# bldc.net
KiCad netlist of a schematic drawn in EAGLE
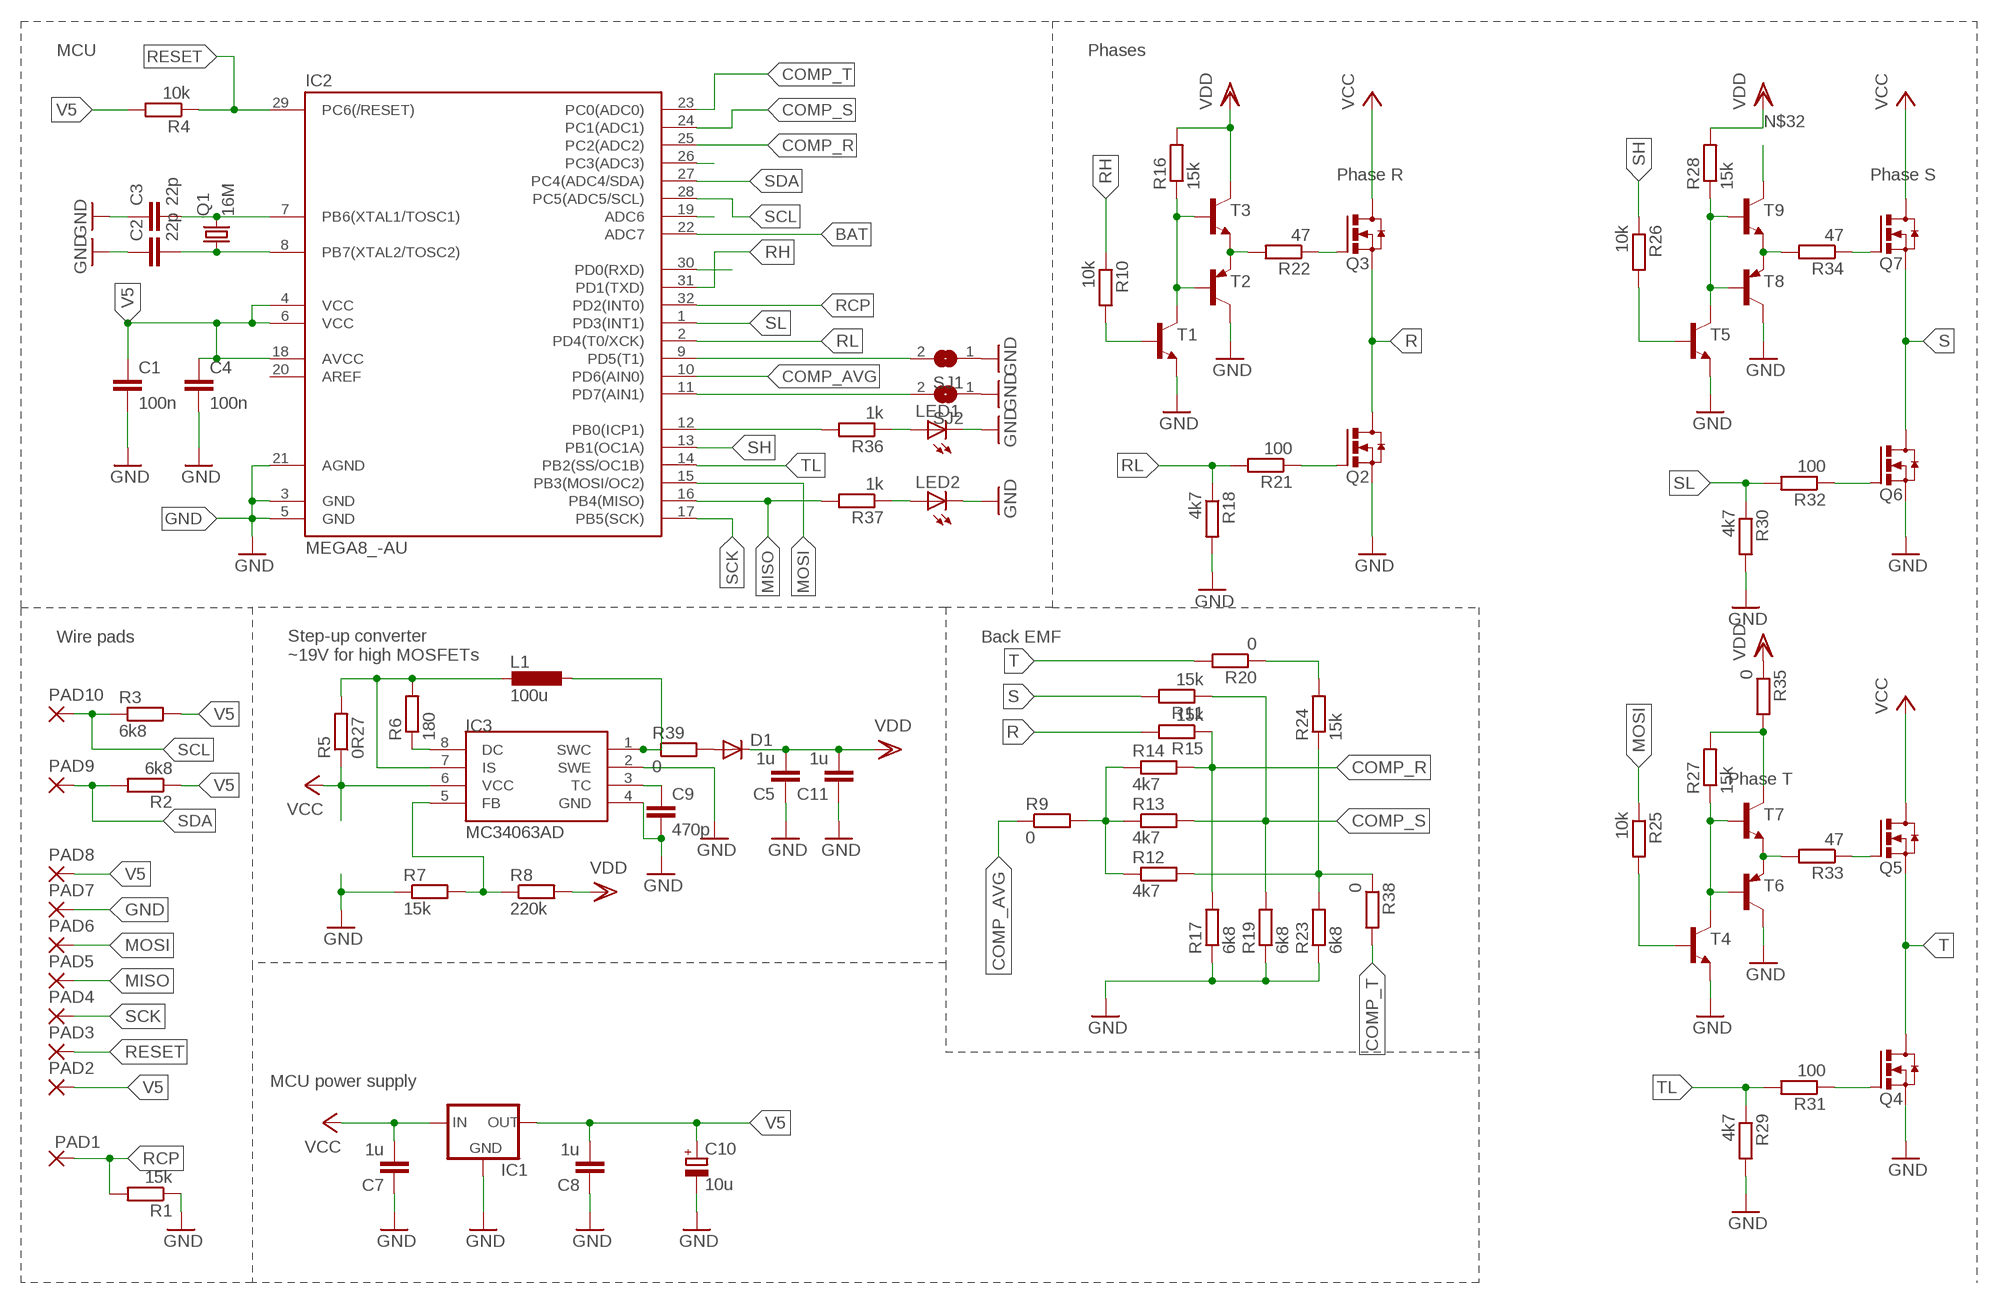
[diagram p0: schematic, sheet 1]

(export (version "E")
  (design (tool "Eeschema 10.0.6"))
  (components
    (comp (ref "C1")
      (value "100n")
      (footprint "eagle-import:C0805K")
      (libsource (lib "eagle-import") (part "rcl2_C-EUC0805K"))
    )
    (comp (ref "C2")
      (value "22p")
      (footprint "eagle-import:C0805K")
      (libsource (lib "eagle-import") (part "rcl2_C-EUC0805K"))
    )
    (comp (ref "C3")
      (value "22p")
      (footprint "eagle-import:C0805K")
      (libsource (lib "eagle-import") (part "rcl2_C-EUC0805K"))
    )
    (comp (ref "C4")
      (value "100n")
      (footprint "eagle-import:C0805K")
      (libsource (lib "eagle-import") (part "rcl2_C-EUC0805K"))
    )
    (comp (ref "C5")
      (value "1u")
      (footprint "eagle-import:C0805K")
      (libsource (lib "eagle-import") (part "rcl2_C-EUC0805K"))
    )
    (comp (ref "C7")
      (value "1u")
      (footprint "eagle-import:C0805K")
      (libsource (lib "eagle-import") (part "rcl2_C-EUC0805K"))
    )
    (comp (ref "C8")
      (value "1u")
      (footprint "eagle-import:C0805K")
      (libsource (lib "eagle-import") (part "rcl2_C-EUC0805K"))
    )
    (comp (ref "C9")
      (value "470p")
      (footprint "eagle-import:C0805K")
      (libsource (lib "eagle-import") (part "C-EUC0805K"))
    )
    (comp (ref "C10")
      (value "10u")
      (footprint "eagle-import:E2,5RE")
      (libsource (lib "eagle-import") (part "CPOL-EUE2.5-4V"))
    )
    (comp (ref "C11")
      (value "1u")
      (footprint "eagle-import:C0805K")
      (libsource (lib "eagle-import") (part "rcl2_C-EUC0805K"))
    )
    (comp (ref "D1")
      (value "DIODE-SOD80C")
      (footprint "eagle-import:SOD80C")
      (libsource (lib "eagle-import") (part "DIODE-SOD80C"))
    )
    (comp (ref "IC1")
      (value "LM1117TO252")
      (footprint "eagle-import:TO252")
      (libsource (lib "eagle-import") (part "LM1117TO252"))
    )
    (comp (ref "IC2")
      (value "MEGA8_-AU")
      (footprint "eagle-import:TQFP32-08")
      (libsource (lib "eagle-import") (part "MEGA8_-AU"))
    )
    (comp (ref "IC3")
      (value "MC34063AD")
      (footprint "eagle-import:SOIC8")
      (libsource (lib "eagle-import") (part "MC34063AD"))
    )
    (comp (ref "L1")
      (value "100u")
      (footprint "eagle-import:0204_7")
      (libsource (lib "eagle-import") (part "L-EU0204/7"))
    )
    (comp (ref "LED1")
      (value "LEDCHIPLED_0805")
      (footprint "eagle-import:CHIPLED_0805")
      (libsource (lib "eagle-import") (part "LEDCHIPLED_0805"))
    )
    (comp (ref "LED2")
      (value "LEDCHIPLED_0805")
      (footprint "eagle-import:CHIPLED_0805")
      (libsource (lib "eagle-import") (part "LEDCHIPLED_0805"))
    )
    (comp (ref "PAD1")
      (value "WIREPADSMD1,27-254")
      (footprint "eagle-import:SMD1,27-2,54")
      (libsource (lib "eagle-import") (part "WIREPADSMD1,27-254"))
    )
    (comp (ref "PAD2")
      (value "WIREPADSMD1,27-254")
      (footprint "eagle-import:SMD1,27-2,54")
      (libsource (lib "eagle-import") (part "WIREPADSMD1,27-254"))
    )
    (comp (ref "PAD3")
      (value "WIREPADSMD1,27-254")
      (footprint "eagle-import:SMD1,27-2,54")
      (libsource (lib "eagle-import") (part "WIREPADSMD1,27-254"))
    )
    (comp (ref "PAD4")
      (value "WIREPADSMD1,27-254")
      (footprint "eagle-import:SMD1,27-2,54")
      (libsource (lib "eagle-import") (part "WIREPADSMD1,27-254"))
    )
    (comp (ref "PAD5")
      (value "WIREPADSMD1,27-254")
      (footprint "eagle-import:SMD1,27-2,54")
      (libsource (lib "eagle-import") (part "WIREPADSMD1,27-254"))
    )
    (comp (ref "PAD6")
      (value "WIREPADSMD1,27-254")
      (footprint "eagle-import:SMD1,27-2,54")
      (libsource (lib "eagle-import") (part "WIREPADSMD1,27-254"))
    )
    (comp (ref "PAD7")
      (value "WIREPADSMD1,27-254")
      (footprint "eagle-import:SMD1,27-2,54")
      (libsource (lib "eagle-import") (part "WIREPADSMD1,27-254"))
    )
    (comp (ref "PAD8")
      (value "WIREPADSMD1,27-254")
      (footprint "eagle-import:SMD1,27-2,54")
      (libsource (lib "eagle-import") (part "WIREPADSMD1,27-254"))
    )
    (comp (ref "PAD9")
      (value "WIREPADSMD1,27-254")
      (footprint "eagle-import:SMD1,27-2,54")
      (libsource (lib "eagle-import") (part "WIREPADSMD1,27-254"))
    )
    (comp (ref "PAD10")
      (value "WIREPADSMD1,27-254")
      (footprint "eagle-import:SMD1,27-2,54")
      (libsource (lib "eagle-import") (part "WIREPADSMD1,27-254"))
    )
    (comp (ref "Q1")
      (value "16M")
      (footprint "eagle-import:SM49")
      (libsource (lib "eagle-import") (part "CRYSTALSM49"))
    )
    (comp (ref "Q2")
      (value "IRFR1205")
      (footprint "eagle-import:D-PAK_TO252AA")
      (libsource (lib "eagle-import") (part "IRFR1205"))
    )
    (comp (ref "Q3")
      (value "IRFR1205")
      (footprint "eagle-import:D-PAK_TO252AA")
      (libsource (lib "eagle-import") (part "IRFR1205"))
    )
    (comp (ref "Q4")
      (value "IRFR1205")
      (footprint "eagle-import:D-PAK_TO252AA")
      (libsource (lib "eagle-import") (part "IRFR1205"))
    )
    (comp (ref "Q5")
      (value "IRFR1205")
      (footprint "eagle-import:D-PAK_TO252AA")
      (libsource (lib "eagle-import") (part "IRFR1205"))
    )
    (comp (ref "Q6")
      (value "IRFR1205")
      (footprint "eagle-import:D-PAK_TO252AA")
      (libsource (lib "eagle-import") (part "IRFR1205"))
    )
    (comp (ref "Q7")
      (value "IRFR1205")
      (footprint "eagle-import:D-PAK_TO252AA")
      (libsource (lib "eagle-import") (part "IRFR1205"))
    )
    (comp (ref "R1")
      (value "15k")
      (footprint "eagle-import:R0805")
      (libsource (lib "eagle-import") (part "R-EU_R0805"))
    )
    (comp (ref "R2")
      (value "6k8")
      (footprint "eagle-import:R0805")
      (libsource (lib "eagle-import") (part "R-EU_R0805"))
    )
    (comp (ref "R3")
      (value "6k8")
      (footprint "eagle-import:R0805")
      (libsource (lib "eagle-import") (part "R-EU_R0805"))
    )
    (comp (ref "R4")
      (value "10k")
      (footprint "eagle-import:R0805")
      (libsource (lib "eagle-import") (part "R-EU_R0805"))
    )
    (comp (ref "R5")
      (value "0R27")
      (footprint "eagle-import:R0805")
      (libsource (lib "eagle-import") (part "R-EU_R0805"))
    )
    (comp (ref "R6")
      (value "180")
      (footprint "eagle-import:R0805")
      (libsource (lib "eagle-import") (part "R-EU_R0805"))
    )
    (comp (ref "R7")
      (value "15k")
      (footprint "eagle-import:R0805")
      (libsource (lib "eagle-import") (part "R-EU_R0805"))
    )
    (comp (ref "R8")
      (value "220k")
      (footprint "eagle-import:R0805")
      (libsource (lib "eagle-import") (part "R-EU_R0805"))
    )
    (comp (ref "R9")
      (value "0")
      (footprint "eagle-import:R0805")
      (libsource (lib "eagle-import") (part "R-EU_R0805"))
    )
    (comp (ref "R10")
      (value "10k")
      (footprint "eagle-import:R0805")
      (libsource (lib "eagle-import") (part "R-EU_R0805"))
    )
    (comp (ref "R11")
      (value "15k")
      (footprint "eagle-import:R0805")
      (libsource (lib "eagle-import") (part "R-EU_R0805"))
    )
    (comp (ref "R12")
      (value "4k7")
      (footprint "eagle-import:R0805")
      (libsource (lib "eagle-import") (part "R-EU_R0805"))
    )
    (comp (ref "R13")
      (value "4k7")
      (footprint "eagle-import:R0805")
      (libsource (lib "eagle-import") (part "R-EU_R0805"))
    )
    (comp (ref "R14")
      (value "4k7")
      (footprint "eagle-import:R0805")
      (libsource (lib "eagle-import") (part "R-EU_R0805"))
    )
    (comp (ref "R15")
      (value "15k")
      (footprint "eagle-import:R0805")
      (libsource (lib "eagle-import") (part "R-EU_R0805"))
    )
    (comp (ref "R16")
      (value "15k")
      (footprint "eagle-import:R0805")
      (libsource (lib "eagle-import") (part "R-EU_R0805"))
    )
    (comp (ref "R17")
      (value "6k8")
      (footprint "eagle-import:R0805")
      (libsource (lib "eagle-import") (part "R-EU_R0805"))
    )
    (comp (ref "R18")
      (value "4k7")
      (footprint "eagle-import:R0805")
      (libsource (lib "eagle-import") (part "R-EU_R0805"))
    )
    (comp (ref "R19")
      (value "6k8")
      (footprint "eagle-import:R0805")
      (libsource (lib "eagle-import") (part "R-EU_R0805"))
    )
    (comp (ref "R20")
      (value "0")
      (footprint "eagle-import:R1206")
      (libsource (lib "eagle-import") (part "R-EU_WIDE1206"))
    )
    (comp (ref "R21")
      (value "100")
      (footprint "eagle-import:R0805")
      (libsource (lib "eagle-import") (part "R-EU_R0805"))
    )
    (comp (ref "R22")
      (value "47")
      (footprint "eagle-import:R0805")
      (libsource (lib "eagle-import") (part "R-EU_R0805"))
    )
    (comp (ref "R23")
      (value "6k8")
      (footprint "eagle-import:R0805")
      (libsource (lib "eagle-import") (part "R-EU_R0805"))
    )
    (comp (ref "R24")
      (value "15k")
      (footprint "eagle-import:R0805")
      (libsource (lib "eagle-import") (part "R-EU_R0805"))
    )
    (comp (ref "R25")
      (value "10k")
      (footprint "eagle-import:R0805")
      (libsource (lib "eagle-import") (part "R-EU_R0805"))
    )
    (comp (ref "R26")
      (value "10k")
      (footprint "eagle-import:R0805")
      (libsource (lib "eagle-import") (part "R-EU_R0805"))
    )
    (comp (ref "R27")
      (value "15k")
      (footprint "eagle-import:R0805")
      (libsource (lib "eagle-import") (part "R-EU_R0805"))
    )
    (comp (ref "R28")
      (value "15k")
      (footprint "eagle-import:R0805")
      (libsource (lib "eagle-import") (part "R-EU_R0805"))
    )
    (comp (ref "R29")
      (value "4k7")
      (footprint "eagle-import:R0805")
      (libsource (lib "eagle-import") (part "R-EU_R0805"))
    )
    (comp (ref "R30")
      (value "4k7")
      (footprint "eagle-import:R0805")
      (libsource (lib "eagle-import") (part "R-EU_R0805"))
    )
    (comp (ref "R31")
      (value "100")
      (footprint "eagle-import:R0805")
      (libsource (lib "eagle-import") (part "R-EU_R0805"))
    )
    (comp (ref "R32")
      (value "100")
      (footprint "eagle-import:R0805")
      (libsource (lib "eagle-import") (part "R-EU_R0805"))
    )
    (comp (ref "R33")
      (value "47")
      (footprint "eagle-import:R0805")
      (libsource (lib "eagle-import") (part "R-EU_R0805"))
    )
    (comp (ref "R34")
      (value "47")
      (footprint "eagle-import:R0805")
      (libsource (lib "eagle-import") (part "R-EU_R0805"))
    )
    (comp (ref "R35")
      (value "0")
      (footprint "eagle-import:R1206")
      (libsource (lib "eagle-import") (part "R-EU_WIDE1206"))
    )
    (comp (ref "R36")
      (value "1k")
      (footprint "eagle-import:R0805")
      (libsource (lib "eagle-import") (part "R-EU_R0805"))
    )
    (comp (ref "R37")
      (value "1k")
      (footprint "eagle-import:R0805")
      (libsource (lib "eagle-import") (part "R-EU_R0805"))
    )
    (comp (ref "R38")
      (value "0")
      (footprint "eagle-import:R0805")
      (libsource (lib "eagle-import") (part "R-EU_R0805"))
    )
    (comp (ref "R39")
      (value "0")
      (footprint "eagle-import:R0805")
      (libsource (lib "eagle-import") (part "R-EU_R0805"))
    )
    (comp (ref "SJ1") (value "SJ") (footprint "eagle-import:SJ") (libsource (lib "eagle-import") (part "SJ")))
    (comp (ref "SJ2") (value "SJ") (footprint "eagle-import:SJ") (libsource (lib "eagle-import") (part "SJ")))
    (comp (ref "T1")
      (value "BC847")
      (footprint "eagle-import:SOT23")
      (libsource (lib "eagle-import") (part "BC847"))
    )
    (comp (ref "T2")
      (value "BC807-16-PNP-SOT23-BEC")
      (footprint "eagle-import:SOT23-BEC")
      (libsource (lib "eagle-import") (part "-PNP-SOT23-BECBC807-16"))
    )
    (comp (ref "T3")
      (value "BC847")
      (footprint "eagle-import:SOT23")
      (libsource (lib "eagle-import") (part "BC847"))
    )
    (comp (ref "T4")
      (value "BC847")
      (footprint "eagle-import:SOT23")
      (libsource (lib "eagle-import") (part "BC847"))
    )
    (comp (ref "T5")
      (value "BC847")
      (footprint "eagle-import:SOT23")
      (libsource (lib "eagle-import") (part "BC847"))
    )
    (comp (ref "T6")
      (value "BC807-16-PNP-SOT23-BEC")
      (footprint "eagle-import:SOT23-BEC")
      (libsource (lib "eagle-import") (part "-PNP-SOT23-BECBC807-16"))
    )
    (comp (ref "T7")
      (value "BC847")
      (footprint "eagle-import:SOT23")
      (libsource (lib "eagle-import") (part "BC847"))
    )
    (comp (ref "T8")
      (value "BC807-16-PNP-SOT23-BEC")
      (footprint "eagle-import:SOT23-BEC")
      (libsource (lib "eagle-import") (part "-PNP-SOT23-BECBC807-16"))
    )
    (comp (ref "T9")
      (value "BC847")
      (footprint "eagle-import:SOT23")
      (libsource (lib "eagle-import") (part "BC847"))
    )
  )
  (nets
    (net (code "1") (name "/N$32") (class "Default")
      (node (ref "R27") (pin "2") (pinfunction "2_2") (pintype "passive"))
      (node (ref "R35") (pin "2") (pinfunction "2_2") (pintype "passive"))
      (node (ref "T7") (pin "3") (pinfunction "C_3") (pintype "passive"))
      (node (ref "T9") (pin "3") (pinfunction "C_3") (pintype "passive"))
    )
    (net (code "2") (name "BAT") (class "Default")
      (node (ref "IC2") (pin "22") (pinfunction "ADC7_22") (pintype "passive"))
    )
    (net (code "3") (name "COMP_AVG") (class "Default")
      (node (ref "IC2") (pin "10") (pinfunction "PD6(AIN0)_10") (pintype "bidirectional"))
      (node (ref "R9") (pin "1") (pinfunction "1_1") (pintype "passive"))
    )
    (net (code "4") (name "COMP_R") (class "Default")
      (node (ref "IC2") (pin "25") (pinfunction "PC2(ADC2)_25") (pintype "bidirectional"))
      (node (ref "R14") (pin "2") (pinfunction "2_2") (pintype "passive"))
      (node (ref "R15") (pin "1") (pinfunction "1_1") (pintype "passive"))
      (node (ref "R17") (pin "2") (pinfunction "2_2") (pintype "passive"))
    )
    (net (code "5") (name "COMP_S") (class "Default")
      (node (ref "IC2") (pin "24") (pinfunction "PC1(ADC1)_24") (pintype "bidirectional"))
      (node (ref "R11") (pin "1") (pinfunction "1_1") (pintype "passive"))
      (node (ref "R13") (pin "2") (pinfunction "2_2") (pintype "passive"))
      (node (ref "R19") (pin "2") (pinfunction "2_2") (pintype "passive"))
    )
    (net (code "6") (name "COMP_T") (class "Default")
      (node (ref "IC2") (pin "23") (pinfunction "PC0(ADC0)_23") (pintype "bidirectional"))
      (node (ref "R38") (pin "2") (pinfunction "2_2") (pintype "passive"))
    )
    (net (code "7") (name "GND") (class "Default")
      (node (ref "C1") (pin "2") (pinfunction "2_2") (pintype "passive"))
      (node (ref "C10") (pin "-") (pinfunction "-_-") (pintype "passive"))
      (node (ref "C11") (pin "1") (pinfunction "1_1") (pintype "passive"))
      (node (ref "C2") (pin "1") (pinfunction "1_1") (pintype "passive"))
      (node (ref "C3") (pin "1") (pinfunction "1_1") (pintype "passive"))
      (node (ref "C4") (pin "2") (pinfunction "2_2") (pintype "passive"))
      (node (ref "C5") (pin "1") (pinfunction "1_1") (pintype "passive"))
      (node (ref "C7") (pin "1") (pinfunction "1_1") (pintype "passive"))
      (node (ref "C8") (pin "1") (pinfunction "1_1") (pintype "passive"))
      (node (ref "C9") (pin "2") (pinfunction "2_2") (pintype "passive"))
      (node (ref "IC1") (pin "1") (pinfunction "GND_1") (pintype "input"))
      (node (ref "IC2") (pin "21") (pinfunction "AGND_21") (pintype "power_in"))
      (node (ref "IC2") (pin "3") (pinfunction "GND_3") (pintype "power_in"))
      (node (ref "IC2") (pin "5") (pinfunction "GND_5") (pintype "power_in"))
      (node (ref "IC3") (pin "2") (pinfunction "SWE_2") (pintype "passive"))
      (node (ref "IC3") (pin "4") (pinfunction "GND_4") (pintype "passive"))
      (node (ref "LED1") (pin "C") (pinfunction "C_C") (pintype "passive"))
      (node (ref "LED2") (pin "C") (pinfunction "C_C") (pintype "passive"))
      (node (ref "PAD7") (pin "1") (pinfunction "P_1") (pintype "passive"))
      (node (ref "Q2") (pin "3") (pinfunction "S_3") (pintype "passive"))
      (node (ref "Q4") (pin "3") (pinfunction "S_3") (pintype "passive"))
      (node (ref "Q6") (pin "3") (pinfunction "S_3") (pintype "passive"))
      (node (ref "R1") (pin "1") (pinfunction "1_1") (pintype "passive"))
      (node (ref "R17") (pin "1") (pinfunction "1_1") (pintype "passive"))
      (node (ref "R18") (pin "2") (pinfunction "2_2") (pintype "passive"))
      (node (ref "R19") (pin "1") (pinfunction "1_1") (pintype "passive"))
      (node (ref "R23") (pin "1") (pinfunction "1_1") (pintype "passive"))
      (node (ref "R29") (pin "2") (pinfunction "2_2") (pintype "passive"))
      (node (ref "R30") (pin "2") (pinfunction "2_2") (pintype "passive"))
      (node (ref "R7") (pin "1") (pinfunction "1_1") (pintype "passive"))
      (node (ref "SJ1") (pin "1") (pinfunction "1_1") (pintype "passive"))
      (node (ref "SJ2") (pin "1") (pinfunction "1_1") (pintype "passive"))
      (node (ref "T1") (pin "2") (pinfunction "E_2") (pintype "passive"))
      (node (ref "T2") (pin "C") (pinfunction "C_C") (pintype "passive"))
      (node (ref "T4") (pin "2") (pinfunction "E_2") (pintype "passive"))
      (node (ref "T5") (pin "2") (pinfunction "E_2") (pintype "passive"))
      (node (ref "T6") (pin "C") (pinfunction "C_C") (pintype "passive"))
      (node (ref "T8") (pin "C") (pinfunction "C_C") (pintype "passive"))
    )
    (net (code "8") (name "MISO") (class "Default")
      (node (ref "IC2") (pin "16") (pinfunction "PB4(MISO)_16") (pintype "bidirectional"))
      (node (ref "PAD5") (pin "1") (pinfunction "P_1") (pintype "passive"))
      (node (ref "R37") (pin "2") (pinfunction "2_2") (pintype "passive"))
    )
    (net (code "9") (name "MOSI") (class "Default")
      (node (ref "IC2") (pin "15") (pinfunction "PB3(MOSI/OC2)_15") (pintype "bidirectional"))
      (node (ref "PAD6") (pin "1") (pinfunction "P_1") (pintype "passive"))
      (node (ref "R25") (pin "1") (pinfunction "1_1") (pintype "passive"))
    )
    (net (code "10") (name "Net-(D1-PadA)") (class "Default")
      (node (ref "D1") (pin "A") (pinfunction "A_A") (pintype "passive"))
      (node (ref "R39") (pin "2") (pinfunction "2_2") (pintype "passive"))
    )
    (net (code "11") (name "Net-(IC2-PB0(ICP1))") (class "Default")
      (node (ref "IC2") (pin "12") (pinfunction "PB0(ICP1)_12") (pintype "bidirectional"))
      (node (ref "R36") (pin "2") (pinfunction "2_2") (pintype "passive"))
    )
    (net (code "12") (name "Net-(IC2-PB6(XTAL1{slash}TOSC1))") (class "Default")
      (node (ref "C3") (pin "2") (pinfunction "2_2") (pintype "passive"))
      (node (ref "IC2") (pin "7") (pinfunction "PB6(XTAL1/TOSC1)_7") (pintype "bidirectional"))
      (node (ref "Q1") (pin "2") (pinfunction "2_2") (pintype "passive"))
    )
    (net (code "13") (name "Net-(IC2-PB7(XTAL2{slash}TOSC2))") (class "Default")
      (node (ref "C2") (pin "2") (pinfunction "2_2") (pintype "passive"))
      (node (ref "IC2") (pin "8") (pinfunction "PB7(XTAL2/TOSC2)_8") (pintype "bidirectional"))
      (node (ref "Q1") (pin "1") (pinfunction "1_1") (pintype "passive"))
    )
    (net (code "14") (name "Net-(IC2-PD5(T1))") (class "Default")
      (node (ref "IC2") (pin "9") (pinfunction "PD5(T1)_9") (pintype "bidirectional"))
      (node (ref "SJ1") (pin "2") (pinfunction "2_2") (pintype "passive"))
    )
    (net (code "15") (name "Net-(IC2-PD7(AIN1))") (class "Default")
      (node (ref "IC2") (pin "11") (pinfunction "PD7(AIN1)_11") (pintype "bidirectional"))
      (node (ref "SJ2") (pin "2") (pinfunction "2_2") (pintype "passive"))
    )
    (net (code "16") (name "Net-(IC3-DC)") (class "Default")
      (node (ref "IC3") (pin "8") (pinfunction "DC_8") (pintype "passive"))
      (node (ref "R6") (pin "1") (pinfunction "1_1") (pintype "passive"))
    )
    (net (code "17") (name "Net-(IC3-FB)") (class "Default")
      (node (ref "IC3") (pin "5") (pinfunction "FB_5") (pintype "passive"))
      (node (ref "R7") (pin "2") (pinfunction "2_2") (pintype "passive"))
      (node (ref "R8") (pin "1") (pinfunction "1_1") (pintype "passive"))
    )
    (net (code "18") (name "Net-(IC3-IS)") (class "Default")
      (node (ref "IC3") (pin "7") (pinfunction "IS_7") (pintype "passive"))
      (node (ref "L1") (pin "2") (pinfunction "2_2") (pintype "passive"))
      (node (ref "R5") (pin "2") (pinfunction "2_2") (pintype "passive"))
      (node (ref "R6") (pin "2") (pinfunction "2_2") (pintype "passive"))
    )
    (net (code "19") (name "Net-(IC3-SWC)") (class "Default")
      (node (ref "IC3") (pin "1") (pinfunction "SWC_1") (pintype "passive"))
      (node (ref "L1") (pin "1") (pinfunction "1_1") (pintype "passive"))
      (node (ref "R39") (pin "1") (pinfunction "1_1") (pintype "passive"))
    )
    (net (code "20") (name "Net-(IC3-TC)") (class "Default")
      (node (ref "C9") (pin "1") (pinfunction "1_1") (pintype "passive"))
      (node (ref "IC3") (pin "3") (pinfunction "TC_3") (pintype "passive"))
    )
    (net (code "21") (name "Net-(LED1-PadA)") (class "Default")
      (node (ref "LED1") (pin "A") (pinfunction "A_A") (pintype "passive"))
      (node (ref "R36") (pin "1") (pinfunction "1_1") (pintype "passive"))
    )
    (net (code "22") (name "Net-(LED2-PadA)") (class "Default")
      (node (ref "LED2") (pin "A") (pinfunction "A_A") (pintype "passive"))
      (node (ref "R37") (pin "1") (pinfunction "1_1") (pintype "passive"))
    )
    (net (code "23") (name "Net-(Q2-G)") (class "Default")
      (node (ref "Q2") (pin "1") (pinfunction "G_1") (pintype "passive"))
      (node (ref "R21") (pin "1") (pinfunction "1_1") (pintype "passive"))
    )
    (net (code "24") (name "Net-(Q3-G)") (class "Default")
      (node (ref "Q3") (pin "1") (pinfunction "G_1") (pintype "passive"))
      (node (ref "R22") (pin "1") (pinfunction "1_1") (pintype "passive"))
    )
    (net (code "25") (name "Net-(Q4-G)") (class "Default")
      (node (ref "Q4") (pin "1") (pinfunction "G_1") (pintype "passive"))
      (node (ref "R31") (pin "1") (pinfunction "1_1") (pintype "passive"))
    )
    (net (code "26") (name "Net-(Q5-G)") (class "Default")
      (node (ref "Q5") (pin "1") (pinfunction "G_1") (pintype "passive"))
      (node (ref "R33") (pin "1") (pinfunction "1_1") (pintype "passive"))
    )
    (net (code "27") (name "Net-(Q6-G)") (class "Default")
      (node (ref "Q6") (pin "1") (pinfunction "G_1") (pintype "passive"))
      (node (ref "R32") (pin "1") (pinfunction "1_1") (pintype "passive"))
    )
    (net (code "28") (name "Net-(Q7-G)") (class "Default")
      (node (ref "Q7") (pin "1") (pinfunction "G_1") (pintype "passive"))
      (node (ref "R34") (pin "1") (pinfunction "1_1") (pintype "passive"))
    )
    (net (code "29") (name "Net-(R12-Pad1)") (class "Default")
      (node (ref "R12") (pin "1") (pinfunction "1_1") (pintype "passive"))
      (node (ref "R13") (pin "1") (pinfunction "1_1") (pintype "passive"))
      (node (ref "R14") (pin "1") (pinfunction "1_1") (pintype "passive"))
      (node (ref "R9") (pin "2") (pinfunction "2_2") (pintype "passive"))
    )
    (net (code "30") (name "Net-(R12-Pad2)") (class "Default")
      (node (ref "R12") (pin "2") (pinfunction "2_2") (pintype "passive"))
      (node (ref "R23") (pin "2") (pinfunction "2_2") (pintype "passive"))
      (node (ref "R24") (pin "1") (pinfunction "1_1") (pintype "passive"))
      (node (ref "R38") (pin "1") (pinfunction "1_1") (pintype "passive"))
    )
    (net (code "31") (name "Net-(R20-Pad1)") (class "Default")
      (node (ref "R20") (pin "1") (pinfunction "1_1") (pintype "passive"))
      (node (ref "R24") (pin "2") (pinfunction "2_2") (pintype "passive"))
    )
    (net (code "32") (name "Net-(T1-B)") (class "Default")
      (node (ref "R10") (pin "2") (pinfunction "2_2") (pintype "passive"))
      (node (ref "T1") (pin "1") (pinfunction "B_1") (pintype "passive"))
    )
    (net (code "33") (name "Net-(T1-C)") (class "Default")
      (node (ref "R16") (pin "1") (pinfunction "1_1") (pintype "passive"))
      (node (ref "T1") (pin "3") (pinfunction "C_3") (pintype "passive"))
      (node (ref "T2") (pin "B") (pinfunction "B_B") (pintype "passive"))
      (node (ref "T3") (pin "1") (pinfunction "B_1") (pintype "passive"))
    )
    (net (code "34") (name "Net-(T3-E)") (class "Default")
      (node (ref "R22") (pin "2") (pinfunction "2_2") (pintype "passive"))
      (node (ref "T2") (pin "E") (pinfunction "E_E") (pintype "passive"))
      (node (ref "T3") (pin "2") (pinfunction "E_2") (pintype "passive"))
    )
    (net (code "35") (name "Net-(T4-B)") (class "Default")
      (node (ref "R25") (pin "2") (pinfunction "2_2") (pintype "passive"))
      (node (ref "T4") (pin "1") (pinfunction "B_1") (pintype "passive"))
    )
    (net (code "36") (name "Net-(T4-C)") (class "Default")
      (node (ref "R27") (pin "1") (pinfunction "1_1") (pintype "passive"))
      (node (ref "T4") (pin "3") (pinfunction "C_3") (pintype "passive"))
      (node (ref "T6") (pin "B") (pinfunction "B_B") (pintype "passive"))
      (node (ref "T7") (pin "1") (pinfunction "B_1") (pintype "passive"))
    )
    (net (code "37") (name "Net-(T5-B)") (class "Default")
      (node (ref "R26") (pin "2") (pinfunction "2_2") (pintype "passive"))
      (node (ref "T5") (pin "1") (pinfunction "B_1") (pintype "passive"))
    )
    (net (code "38") (name "Net-(T5-C)") (class "Default")
      (node (ref "R28") (pin "1") (pinfunction "1_1") (pintype "passive"))
      (node (ref "T5") (pin "3") (pinfunction "C_3") (pintype "passive"))
      (node (ref "T8") (pin "B") (pinfunction "B_B") (pintype "passive"))
      (node (ref "T9") (pin "1") (pinfunction "B_1") (pintype "passive"))
    )
    (net (code "39") (name "Net-(T7-E)") (class "Default")
      (node (ref "R33") (pin "2") (pinfunction "2_2") (pintype "passive"))
      (node (ref "T6") (pin "E") (pinfunction "E_E") (pintype "passive"))
      (node (ref "T7") (pin "2") (pinfunction "E_2") (pintype "passive"))
    )
    (net (code "40") (name "Net-(T9-E)") (class "Default")
      (node (ref "R34") (pin "2") (pinfunction "2_2") (pintype "passive"))
      (node (ref "T8") (pin "E") (pinfunction "E_E") (pintype "passive"))
      (node (ref "T9") (pin "2") (pinfunction "E_2") (pintype "passive"))
    )
    (net (code "41") (name "R") (class "Default")
      (node (ref "Q2") (pin "4") (pinfunction "D_4") (pintype "passive"))
      (node (ref "Q3") (pin "3") (pinfunction "S_3") (pintype "passive"))
      (node (ref "R15") (pin "2") (pinfunction "2_2") (pintype "passive"))
    )
    (net (code "42") (name "RCP") (class "Default")
      (node (ref "IC2") (pin "32") (pinfunction "PD2(INT0)_32") (pintype "bidirectional"))
      (node (ref "PAD1") (pin "1") (pinfunction "P_1") (pintype "passive"))
      (node (ref "R1") (pin "2") (pinfunction "2_2") (pintype "passive"))
    )
    (net (code "43") (name "RESET") (class "Default")
      (node (ref "IC2") (pin "29") (pinfunction "PC6(/RESET)_29") (pintype "bidirectional"))
      (node (ref "PAD3") (pin "1") (pinfunction "P_1") (pintype "passive"))
      (node (ref "R4") (pin "1") (pinfunction "1_1") (pintype "passive"))
    )
    (net (code "44") (name "RH") (class "Default")
      (node (ref "IC2") (pin "31") (pinfunction "PD1(TXD)_31") (pintype "bidirectional"))
      (node (ref "R10") (pin "1") (pinfunction "1_1") (pintype "passive"))
    )
    (net (code "45") (name "RL") (class "Default")
      (node (ref "IC2") (pin "2") (pinfunction "PD4(T0/XCK)_2") (pintype "bidirectional"))
      (node (ref "R18") (pin "1") (pinfunction "1_1") (pintype "passive"))
      (node (ref "R21") (pin "2") (pinfunction "2_2") (pintype "passive"))
    )
    (net (code "46") (name "S") (class "Default")
      (node (ref "Q6") (pin "4") (pinfunction "D_4") (pintype "passive"))
      (node (ref "Q7") (pin "3") (pinfunction "S_3") (pintype "passive"))
      (node (ref "R11") (pin "2") (pinfunction "2_2") (pintype "passive"))
    )
    (net (code "47") (name "SCK") (class "Default")
      (node (ref "IC2") (pin "17") (pinfunction "PB5(SCK)_17") (pintype "bidirectional"))
      (node (ref "PAD4") (pin "1") (pinfunction "P_1") (pintype "passive"))
    )
    (net (code "48") (name "SCL") (class "Default")
      (node (ref "IC2") (pin "28") (pinfunction "PC5(ADC5/SCL)_28") (pintype "bidirectional"))
      (node (ref "PAD10") (pin "1") (pinfunction "P_1") (pintype "passive"))
      (node (ref "R3") (pin "1") (pinfunction "1_1") (pintype "passive"))
    )
    (net (code "49") (name "SDA") (class "Default")
      (node (ref "IC2") (pin "27") (pinfunction "PC4(ADC4/SDA)_27") (pintype "bidirectional"))
      (node (ref "PAD9") (pin "1") (pinfunction "P_1") (pintype "passive"))
      (node (ref "R2") (pin "2") (pinfunction "2_2") (pintype "passive"))
    )
    (net (code "50") (name "SH") (class "Default")
      (node (ref "IC2") (pin "13") (pinfunction "PB1(OC1A)_13") (pintype "bidirectional"))
      (node (ref "R26") (pin "1") (pinfunction "1_1") (pintype "passive"))
    )
    (net (code "51") (name "SL") (class "Default")
      (node (ref "IC2") (pin "1") (pinfunction "PD3(INT1)_1") (pintype "bidirectional"))
      (node (ref "R30") (pin "1") (pinfunction "1_1") (pintype "passive"))
      (node (ref "R32") (pin "2") (pinfunction "2_2") (pintype "passive"))
    )
    (net (code "52") (name "T") (class "Default")
      (node (ref "Q4") (pin "4") (pinfunction "D_4") (pintype "passive"))
      (node (ref "Q5") (pin "3") (pinfunction "S_3") (pintype "passive"))
      (node (ref "R20") (pin "2") (pinfunction "2_2") (pintype "passive"))
    )
    (net (code "53") (name "TL") (class "Default")
      (node (ref "IC2") (pin "14") (pinfunction "PB2(SS/OC1B)_14") (pintype "bidirectional"))
      (node (ref "R29") (pin "1") (pinfunction "1_1") (pintype "passive"))
      (node (ref "R31") (pin "2") (pinfunction "2_2") (pintype "passive"))
    )
    (net (code "54") (name "V5") (class "Default")
      (node (ref "C1") (pin "1") (pinfunction "1_1") (pintype "passive"))
      (node (ref "C10") (pin "+") (pinfunction "+_+") (pintype "passive"))
      (node (ref "C4") (pin "1") (pinfunction "1_1") (pintype "passive"))
      (node (ref "C8") (pin "2") (pinfunction "2_2") (pintype "passive"))
      (node (ref "IC1") (pin "3") (pinfunction "OUT_3") (pintype "passive"))
      (node (ref "IC2") (pin "18") (pinfunction "AVCC_18") (pintype "passive"))
      (node (ref "IC2") (pin "4") (pinfunction "VCC_4") (pintype "power_in"))
      (node (ref "IC2") (pin "6") (pinfunction "VCC_6") (pintype "power_in"))
      (node (ref "PAD2") (pin "1") (pinfunction "P_1") (pintype "passive"))
      (node (ref "PAD8") (pin "1") (pinfunction "P_1") (pintype "passive"))
      (node (ref "R2") (pin "1") (pinfunction "1_1") (pintype "passive"))
      (node (ref "R3") (pin "2") (pinfunction "2_2") (pintype "passive"))
      (node (ref "R4") (pin "2") (pinfunction "2_2") (pintype "passive"))
    )
    (net (code "55") (name "VCC") (class "Default")
      (node (ref "C7") (pin "2") (pinfunction "2_2") (pintype "passive"))
      (node (ref "IC1") (pin "2") (pinfunction "IN_2") (pintype "input"))
      (node (ref "IC3") (pin "6") (pinfunction "VCC_6") (pintype "passive"))
      (node (ref "Q3") (pin "4") (pinfunction "D_4") (pintype "passive"))
      (node (ref "Q5") (pin "4") (pinfunction "D_4") (pintype "passive"))
      (node (ref "Q7") (pin "4") (pinfunction "D_4") (pintype "passive"))
      (node (ref "R5") (pin "1") (pinfunction "1_1") (pintype "passive"))
    )
    (net (code "56") (name "VDD") (class "Default")
      (node (ref "C11") (pin "2") (pinfunction "2_2") (pintype "passive"))
      (node (ref "C5") (pin "2") (pinfunction "2_2") (pintype "passive"))
      (node (ref "D1") (pin "C") (pinfunction "C_C") (pintype "passive"))
      (node (ref "R16") (pin "2") (pinfunction "2_2") (pintype "passive"))
      (node (ref "R28") (pin "2") (pinfunction "2_2") (pintype "passive"))
      (node (ref "R35") (pin "1") (pinfunction "1_1") (pintype "passive"))
      (node (ref "R8") (pin "2") (pinfunction "2_2") (pintype "passive"))
      (node (ref "T3") (pin "3") (pinfunction "C_3") (pintype "passive"))
    )
    (net (code "57") (name "unconnected-(IC2-ADC6-Pad19)") (class "Default")
      (node (ref "IC2") (pin "19") (pinfunction "ADC6_19") (pintype "passive"))
    )
    (net (code "58") (name "unconnected-(IC2-AREF-Pad20)") (class "Default")
      (node (ref "IC2") (pin "20") (pinfunction "AREF_20") (pintype "passive"))
    )
    (net (code "59") (name "unconnected-(IC2-PC3(ADC3)-Pad26)") (class "Default")
      (node (ref "IC2") (pin "26") (pinfunction "PC3(ADC3)_26") (pintype "bidirectional"))
    )
    (net (code "60") (name "unconnected-(IC2-PD0(RXD)-Pad30)") (class "Default")
      (node (ref "IC2") (pin "30") (pinfunction "PD0(RXD)_30") (pintype "bidirectional"))
    )
  )
)
